# ESQUEMATICO.net
KiCad netlist of a schematic drawn in Altium Designer
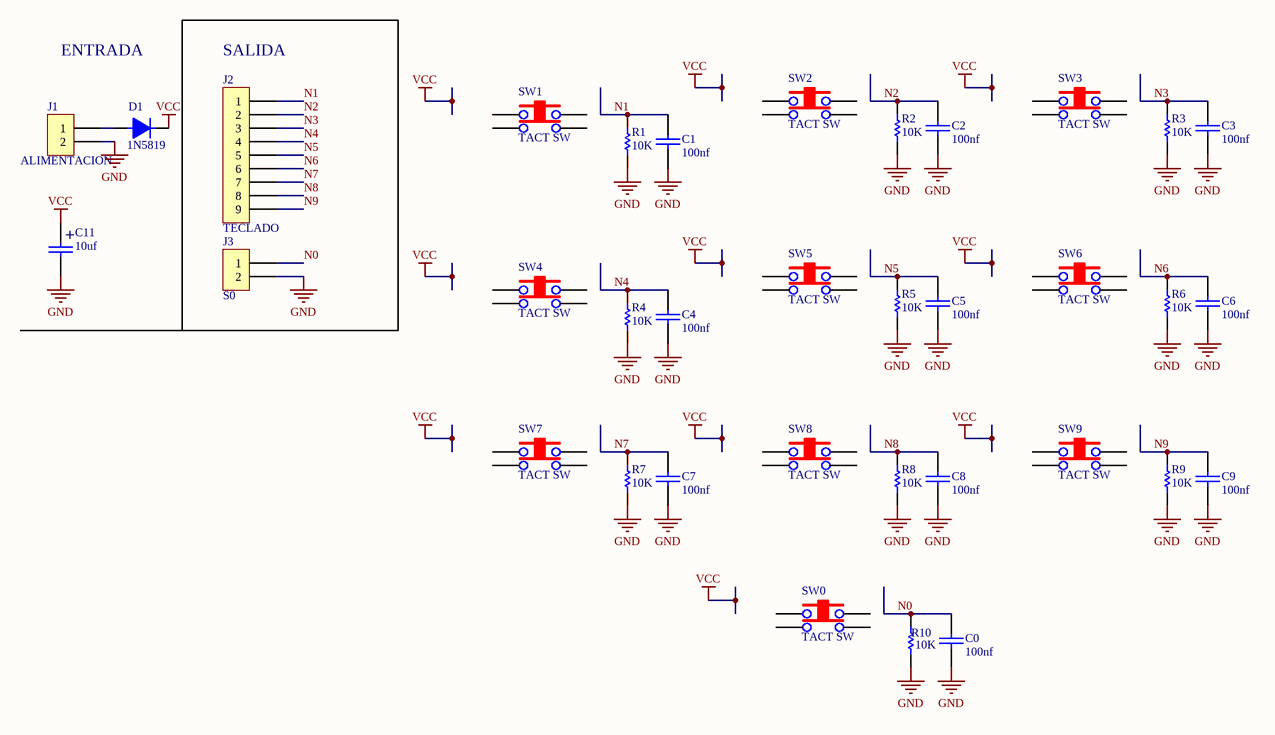
[diagram p0: ESQUEMATICO.SchDoc]

(export (version "E")
  (design (tool "Eeschema 10.0.6"))
  (components
    (comp (ref "C0") (value "100nf") (footprint "CAP200") (libsource (lib "LIBEBAL") (part "CAP")))
    (comp (ref "C1") (value "100nf") (footprint "CAP200") (libsource (lib "LIBEBAL") (part "CAP")))
    (comp (ref "C2") (value "100nf") (footprint "CAP200") (libsource (lib "LIBEBAL") (part "CAP")))
    (comp (ref "C3") (value "100nf") (footprint "CAP200") (libsource (lib "LIBEBAL") (part "CAP")))
    (comp (ref "C4") (value "100nf") (footprint "CAP200") (libsource (lib "LIBEBAL") (part "CAP")))
    (comp (ref "C5") (value "100nf") (footprint "CAP200") (libsource (lib "LIBEBAL") (part "CAP")))
    (comp (ref "C6") (value "100nf") (footprint "CAP200") (libsource (lib "LIBEBAL") (part "CAP")))
    (comp (ref "C7") (value "100nf") (footprint "CAP200") (libsource (lib "LIBEBAL") (part "CAP")))
    (comp (ref "C8") (value "100nf") (footprint "CAP200") (libsource (lib "LIBEBAL") (part "CAP")))
    (comp (ref "C9") (value "100nf") (footprint "CAP200") (libsource (lib "LIBEBAL") (part "CAP")))
    (comp (ref "C11") (value "10uf") (footprint "CAP100RP") (libsource (lib "Libreria4") (part "CAPPOL")))
    (comp (ref "D1") (value "1N5819") (footprint "DO41") (libsource (lib "Libreria4") (part "DIODO")))
    (comp (ref "J1")
      (value "ALIMENTACION")
      (footprint "BORNERA2")
      (libsource (lib "LIBEBAL") (part "BORNERA 2"))
    )
    (comp (ref "J2") (value "TECLADO") (footprint "BORNERA9") (libsource (lib "LIBEBAL") (part "BORNERA 9")))
    (comp (ref "J3") (value "S0") (footprint "BORNERA2") (libsource (lib "LIBEBAL") (part "BORNERA 2")))
    (comp (ref "R1") (value "10K") (footprint "RES400") (libsource (lib "LIBEBAL") (part "RES")))
    (comp (ref "R2") (value "10K") (footprint "RES400") (libsource (lib "LIBEBAL") (part "RES")))
    (comp (ref "R3") (value "10K") (footprint "RES400") (libsource (lib "LIBEBAL") (part "RES")))
    (comp (ref "R4") (value "10K") (footprint "RES400") (libsource (lib "LIBEBAL") (part "RES")))
    (comp (ref "R5") (value "10K") (footprint "RES400") (libsource (lib "LIBEBAL") (part "RES")))
    (comp (ref "R6") (value "10K") (footprint "RES400") (libsource (lib "LIBEBAL") (part "RES")))
    (comp (ref "R7") (value "10K") (footprint "RES400") (libsource (lib "LIBEBAL") (part "RES")))
    (comp (ref "R8") (value "10K") (footprint "RES400") (libsource (lib "LIBEBAL") (part "RES")))
    (comp (ref "R9") (value "10K") (footprint "RES400") (libsource (lib "LIBEBAL") (part "RES")))
    (comp (ref "R10") (value "10K") (footprint "RES400") (libsource (lib "LIBEBAL") (part "RES")))
    (comp (ref "SW0")
      (value "TACT SW")
      (footprint "TACTSWITCH")
      (description "Pulsador")
      (fields (field (name "AUTOR") "Guido Spataro"))
      (libsource (lib "Schlib1") (part "Pulsador"))
    )
    (comp (ref "SW1")
      (value "TACT SW")
      (footprint "TACTSWITCH")
      (description "Pulsador")
      (fields (field (name "AUTOR") "Guido Spataro"))
      (libsource (lib "Schlib1") (part "Pulsador"))
    )
    (comp (ref "SW2")
      (value "TACT SW")
      (footprint "TACTSWITCH")
      (description "Pulsador")
      (fields (field (name "AUTOR") "Guido Spataro"))
      (libsource (lib "Schlib1") (part "Pulsador"))
    )
    (comp (ref "SW3")
      (value "TACT SW")
      (footprint "TACTSWITCH")
      (description "Pulsador")
      (fields (field (name "AUTOR") "Guido Spataro"))
      (libsource (lib "Schlib1") (part "Pulsador"))
    )
    (comp (ref "SW4")
      (value "TACT SW")
      (footprint "TACTSWITCH")
      (description "Pulsador")
      (fields (field (name "AUTOR") "Guido Spataro"))
      (libsource (lib "Schlib1") (part "Pulsador"))
    )
    (comp (ref "SW5")
      (value "TACT SW")
      (footprint "TACTSWITCH")
      (description "Pulsador")
      (fields (field (name "AUTOR") "Guido Spataro"))
      (libsource (lib "Schlib1") (part "Pulsador"))
    )
    (comp (ref "SW6")
      (value "TACT SW")
      (footprint "TACTSWITCH")
      (description "Pulsador")
      (fields (field (name "AUTOR") "Guido Spataro"))
      (libsource (lib "Schlib1") (part "Pulsador"))
    )
    (comp (ref "SW7")
      (value "TACT SW")
      (footprint "TACTSWITCH")
      (description "Pulsador")
      (fields (field (name "AUTOR") "Guido Spataro"))
      (libsource (lib "Schlib1") (part "Pulsador"))
    )
    (comp (ref "SW8")
      (value "TACT SW")
      (footprint "TACTSWITCH")
      (description "Pulsador")
      (fields (field (name "AUTOR") "Guido Spataro"))
      (libsource (lib "Schlib1") (part "Pulsador"))
    )
    (comp (ref "SW9")
      (value "TACT SW")
      (footprint "TACTSWITCH")
      (description "Pulsador")
      (fields (field (name "AUTOR") "Guido Spataro"))
      (libsource (lib "Schlib1") (part "Pulsador"))
    )
  )
  (nets
    (net (code "1") (name "/N0") (class "Default")
      (node (ref "C0") (pin "1") (pinfunction "1_1") (pintype "passive"))
      (node (ref "J3") (pin "1") (pinfunction "1_1") (pintype "passive"))
      (node (ref "R10") (pin "2") (pinfunction "2_2") (pintype "passive"))
    )
    (net (code "2") (name "/N1") (class "Default")
      (node (ref "C1") (pin "1") (pinfunction "1_1") (pintype "passive"))
      (node (ref "J2") (pin "1") (pinfunction "1_1") (pintype "passive"))
      (node (ref "R1") (pin "2") (pinfunction "2_2") (pintype "passive"))
    )
    (net (code "3") (name "/N2") (class "Default")
      (node (ref "C2") (pin "1") (pinfunction "1_1") (pintype "passive"))
      (node (ref "J2") (pin "2") (pinfunction "2_2") (pintype "passive"))
      (node (ref "R2") (pin "2") (pinfunction "2_2") (pintype "passive"))
    )
    (net (code "4") (name "/N3") (class "Default")
      (node (ref "C3") (pin "1") (pinfunction "1_1") (pintype "passive"))
      (node (ref "J2") (pin "3") (pinfunction "3_3") (pintype "passive"))
      (node (ref "R3") (pin "2") (pinfunction "2_2") (pintype "passive"))
    )
    (net (code "5") (name "/N4") (class "Default")
      (node (ref "C4") (pin "1") (pinfunction "1_1") (pintype "passive"))
      (node (ref "J2") (pin "4") (pinfunction "4_4") (pintype "passive"))
      (node (ref "R4") (pin "2") (pinfunction "2_2") (pintype "passive"))
    )
    (net (code "6") (name "/N5") (class "Default")
      (node (ref "C5") (pin "1") (pinfunction "1_1") (pintype "passive"))
      (node (ref "J2") (pin "5") (pinfunction "5_5") (pintype "passive"))
      (node (ref "R5") (pin "2") (pinfunction "2_2") (pintype "passive"))
    )
    (net (code "7") (name "/N6") (class "Default")
      (node (ref "C6") (pin "1") (pinfunction "1_1") (pintype "passive"))
      (node (ref "J2") (pin "6") (pinfunction "6_6") (pintype "passive"))
      (node (ref "R6") (pin "2") (pinfunction "2_2") (pintype "passive"))
    )
    (net (code "8") (name "/N7") (class "Default")
      (node (ref "C7") (pin "1") (pinfunction "1_1") (pintype "passive"))
      (node (ref "J2") (pin "7") (pinfunction "7_7") (pintype "passive"))
      (node (ref "R7") (pin "2") (pinfunction "2_2") (pintype "passive"))
    )
    (net (code "9") (name "/N8") (class "Default")
      (node (ref "C8") (pin "1") (pinfunction "1_1") (pintype "passive"))
      (node (ref "J2") (pin "8") (pinfunction "8_8") (pintype "passive"))
      (node (ref "R8") (pin "2") (pinfunction "2_2") (pintype "passive"))
    )
    (net (code "10") (name "/N9") (class "Default")
      (node (ref "C9") (pin "1") (pinfunction "1_1") (pintype "passive"))
      (node (ref "J2") (pin "9") (pinfunction "9_9") (pintype "passive"))
      (node (ref "R9") (pin "2") (pinfunction "2_2") (pintype "passive"))
    )
    (net (code "11") (name "GND") (class "Default")
      (node (ref "C0") (pin "2") (pinfunction "2_2") (pintype "passive"))
      (node (ref "C1") (pin "2") (pinfunction "2_2") (pintype "passive"))
      (node (ref "C11") (pin "2") (pinfunction "2_2") (pintype "passive"))
      (node (ref "C2") (pin "2") (pinfunction "2_2") (pintype "passive"))
      (node (ref "C3") (pin "2") (pinfunction "2_2") (pintype "passive"))
      (node (ref "C4") (pin "2") (pinfunction "2_2") (pintype "passive"))
      (node (ref "C5") (pin "2") (pinfunction "2_2") (pintype "passive"))
      (node (ref "C6") (pin "2") (pinfunction "2_2") (pintype "passive"))
      (node (ref "C7") (pin "2") (pinfunction "2_2") (pintype "passive"))
      (node (ref "C8") (pin "2") (pinfunction "2_2") (pintype "passive"))
      (node (ref "C9") (pin "2") (pinfunction "2_2") (pintype "passive"))
      (node (ref "J1") (pin "2") (pinfunction "2_2") (pintype "passive"))
      (node (ref "J3") (pin "2") (pinfunction "2_2") (pintype "passive"))
      (node (ref "R1") (pin "1") (pinfunction "1_1") (pintype "passive"))
      (node (ref "R10") (pin "1") (pinfunction "1_1") (pintype "passive"))
      (node (ref "R2") (pin "1") (pinfunction "1_1") (pintype "passive"))
      (node (ref "R3") (pin "1") (pinfunction "1_1") (pintype "passive"))
      (node (ref "R4") (pin "1") (pinfunction "1_1") (pintype "passive"))
      (node (ref "R5") (pin "1") (pinfunction "1_1") (pintype "passive"))
      (node (ref "R6") (pin "1") (pinfunction "1_1") (pintype "passive"))
      (node (ref "R7") (pin "1") (pinfunction "1_1") (pintype "passive"))
      (node (ref "R8") (pin "1") (pinfunction "1_1") (pintype "passive"))
      (node (ref "R9") (pin "1") (pinfunction "1_1") (pintype "passive"))
    )
    (net (code "12") (name "Net-(D1-Pad1)") (class "Default")
      (node (ref "D1") (pin "1") (pinfunction "1_1") (pintype "passive"))
      (node (ref "J1") (pin "1") (pinfunction "1_1") (pintype "passive"))
    )
    (net (code "13") (name "VCC") (class "Default")
      (node (ref "C11") (pin "1") (pinfunction "1_1") (pintype "passive"))
      (node (ref "D1") (pin "2") (pinfunction "2_2") (pintype "passive"))
    )
    (net (code "14") (name "unconnected-(SW0-Pad1)") (class "Default")
      (node (ref "SW0") (pin "1") (pinfunction "1_1") (pintype "passive"))
    )
    (net (code "15") (name "unconnected-(SW0-Pad2)") (class "Default")
      (node (ref "SW0") (pin "2") (pinfunction "2_2") (pintype "passive"))
    )
    (net (code "16") (name "unconnected-(SW0-Pad3)") (class "Default")
      (node (ref "SW0") (pin "3") (pinfunction "3_3") (pintype "passive"))
    )
    (net (code "17") (name "unconnected-(SW0-Pad4)") (class "Default")
      (node (ref "SW0") (pin "4") (pinfunction "4_4") (pintype "passive"))
    )
    (net (code "18") (name "unconnected-(SW1-Pad1)") (class "Default")
      (node (ref "SW1") (pin "1") (pinfunction "1_1") (pintype "passive"))
    )
    (net (code "19") (name "unconnected-(SW1-Pad2)") (class "Default")
      (node (ref "SW1") (pin "2") (pinfunction "2_2") (pintype "passive"))
    )
    (net (code "20") (name "unconnected-(SW1-Pad3)") (class "Default")
      (node (ref "SW1") (pin "3") (pinfunction "3_3") (pintype "passive"))
    )
    (net (code "21") (name "unconnected-(SW1-Pad4)") (class "Default")
      (node (ref "SW1") (pin "4") (pinfunction "4_4") (pintype "passive"))
    )
    (net (code "22") (name "unconnected-(SW2-Pad1)") (class "Default")
      (node (ref "SW2") (pin "1") (pinfunction "1_1") (pintype "passive"))
    )
    (net (code "23") (name "unconnected-(SW2-Pad2)") (class "Default")
      (node (ref "SW2") (pin "2") (pinfunction "2_2") (pintype "passive"))
    )
    (net (code "24") (name "unconnected-(SW2-Pad3)") (class "Default")
      (node (ref "SW2") (pin "3") (pinfunction "3_3") (pintype "passive"))
    )
    (net (code "25") (name "unconnected-(SW2-Pad4)") (class "Default")
      (node (ref "SW2") (pin "4") (pinfunction "4_4") (pintype "passive"))
    )
    (net (code "26") (name "unconnected-(SW3-Pad1)") (class "Default")
      (node (ref "SW3") (pin "1") (pinfunction "1_1") (pintype "passive"))
    )
    (net (code "27") (name "unconnected-(SW3-Pad2)") (class "Default")
      (node (ref "SW3") (pin "2") (pinfunction "2_2") (pintype "passive"))
    )
    (net (code "28") (name "unconnected-(SW3-Pad3)") (class "Default")
      (node (ref "SW3") (pin "3") (pinfunction "3_3") (pintype "passive"))
    )
    (net (code "29") (name "unconnected-(SW3-Pad4)") (class "Default")
      (node (ref "SW3") (pin "4") (pinfunction "4_4") (pintype "passive"))
    )
    (net (code "30") (name "unconnected-(SW4-Pad1)") (class "Default")
      (node (ref "SW4") (pin "1") (pinfunction "1_1") (pintype "passive"))
    )
    (net (code "31") (name "unconnected-(SW4-Pad2)") (class "Default")
      (node (ref "SW4") (pin "2") (pinfunction "2_2") (pintype "passive"))
    )
    (net (code "32") (name "unconnected-(SW4-Pad3)") (class "Default")
      (node (ref "SW4") (pin "3") (pinfunction "3_3") (pintype "passive"))
    )
    (net (code "33") (name "unconnected-(SW4-Pad4)") (class "Default")
      (node (ref "SW4") (pin "4") (pinfunction "4_4") (pintype "passive"))
    )
    (net (code "34") (name "unconnected-(SW5-Pad1)") (class "Default")
      (node (ref "SW5") (pin "1") (pinfunction "1_1") (pintype "passive"))
    )
    (net (code "35") (name "unconnected-(SW5-Pad2)") (class "Default")
      (node (ref "SW5") (pin "2") (pinfunction "2_2") (pintype "passive"))
    )
    (net (code "36") (name "unconnected-(SW5-Pad3)") (class "Default")
      (node (ref "SW5") (pin "3") (pinfunction "3_3") (pintype "passive"))
    )
    (net (code "37") (name "unconnected-(SW5-Pad4)") (class "Default")
      (node (ref "SW5") (pin "4") (pinfunction "4_4") (pintype "passive"))
    )
    (net (code "38") (name "unconnected-(SW6-Pad1)") (class "Default")
      (node (ref "SW6") (pin "1") (pinfunction "1_1") (pintype "passive"))
    )
    (net (code "39") (name "unconnected-(SW6-Pad2)") (class "Default")
      (node (ref "SW6") (pin "2") (pinfunction "2_2") (pintype "passive"))
    )
    (net (code "40") (name "unconnected-(SW6-Pad3)") (class "Default")
      (node (ref "SW6") (pin "3") (pinfunction "3_3") (pintype "passive"))
    )
    (net (code "41") (name "unconnected-(SW6-Pad4)") (class "Default")
      (node (ref "SW6") (pin "4") (pinfunction "4_4") (pintype "passive"))
    )
    (net (code "42") (name "unconnected-(SW7-Pad1)") (class "Default")
      (node (ref "SW7") (pin "1") (pinfunction "1_1") (pintype "passive"))
    )
    (net (code "43") (name "unconnected-(SW7-Pad2)") (class "Default")
      (node (ref "SW7") (pin "2") (pinfunction "2_2") (pintype "passive"))
    )
    (net (code "44") (name "unconnected-(SW7-Pad3)") (class "Default")
      (node (ref "SW7") (pin "3") (pinfunction "3_3") (pintype "passive"))
    )
    (net (code "45") (name "unconnected-(SW7-Pad4)") (class "Default")
      (node (ref "SW7") (pin "4") (pinfunction "4_4") (pintype "passive"))
    )
    (net (code "46") (name "unconnected-(SW8-Pad1)") (class "Default")
      (node (ref "SW8") (pin "1") (pinfunction "1_1") (pintype "passive"))
    )
    (net (code "47") (name "unconnected-(SW8-Pad2)") (class "Default")
      (node (ref "SW8") (pin "2") (pinfunction "2_2") (pintype "passive"))
    )
    (net (code "48") (name "unconnected-(SW8-Pad3)") (class "Default")
      (node (ref "SW8") (pin "3") (pinfunction "3_3") (pintype "passive"))
    )
    (net (code "49") (name "unconnected-(SW8-Pad4)") (class "Default")
      (node (ref "SW8") (pin "4") (pinfunction "4_4") (pintype "passive"))
    )
    (net (code "50") (name "unconnected-(SW9-Pad1)") (class "Default")
      (node (ref "SW9") (pin "1") (pinfunction "1_1") (pintype "passive"))
    )
    (net (code "51") (name "unconnected-(SW9-Pad2)") (class "Default")
      (node (ref "SW9") (pin "2") (pinfunction "2_2") (pintype "passive"))
    )
    (net (code "52") (name "unconnected-(SW9-Pad3)") (class "Default")
      (node (ref "SW9") (pin "3") (pinfunction "3_3") (pintype "passive"))
    )
    (net (code "53") (name "unconnected-(SW9-Pad4)") (class "Default")
      (node (ref "SW9") (pin "4") (pinfunction "4_4") (pintype "passive"))
    )
  )
)
